# RPL_POWER_SOLENOIDS_REV2.net
KiCad netlist of a schematic drawn in Altium Designer
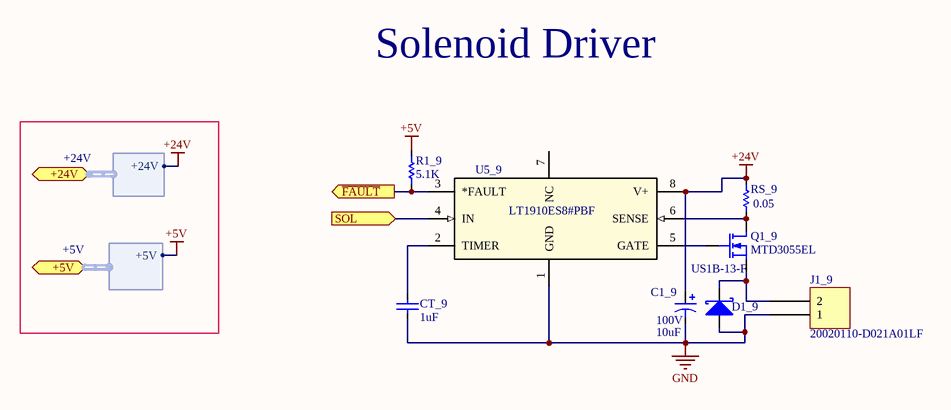
[diagram p0: RPL_POWER_SOLENOIDS_REV2.SchDoc]

(export (version "E")
  (design (tool "Eeschema 10.0.6"))
  (components
    (comp (ref "C1_9")
      (value "100V")
      (footprint "CAPs:(1210) CAPC3225X280")
      (fields (field (name "ALTIUM_VALUE") "10uF"))
      (libsource (lib "Generic_Library") (part "Cap Elec"))
    )
    (comp (ref "CT_9")
      (value "1uF")
      (footprint "(1210) CAPC3225X280")
      (fields (field (name "Comment") "Cap"))
      (libsource (lib "Generic_Library") (part "Cap"))
    )
    (comp (ref "D1_9")
      (value "US1B-13-F")
      (footprint "Diods:US1B-13-F")
      (libsource (lib "Generic_Library") (part "Diod"))
    )
    (comp (ref "J1_9")
      (value "20020110-D021A01LF")
      (footprint "FCI 06-381-2PIN")
      (description "TERM BLOCK HDR 2POS R/A 3.81MM")
      (fields (field (name "MANUFACTURER") "FCI") (field (name "VOLTAGE") "300V"))
      (libsource (lib "Celestial Library Database") (part "2 Pin"))
    )
    (comp (ref "Q1_9")
      (value "MTD3055EL")
      (footprint "TO229P990X239-3N")
      (libsource (lib "Generic_Library") (part "Mosfet"))
    )
    (comp (ref "R1_9")
      (value "5.1K")
      (footprint "SMD Resistors:RES 0805")
      (fields (field (name "Comment") "Res"))
      (libsource (lib "Generic_Library") (part "Res"))
    )
    (comp (ref "RS_9")
      (value "0.05")
      (footprint "SMD Resistors:RES 1206")
      (fields (field (name "Comment") "Res"))
      (libsource (lib "Generic_Library") (part "Res"))
    )
    (comp (ref "U5_9")
      (value "LT1910ES8#PBF")
      (footprint "LT1910:SO-8_S")
      (description "Imported")
      (fields (field (name "MANUFACTURER_PART_NUMBER") "lt1910es8#pbf"))
      (libsource (lib "Generic_Library") (part "LT1910ES8#PBF"))
    )
  )
  (nets
    (net (code "1") (name "+5V") (class "Default")
      (node (ref "R1_9") (pin "2") (pinfunction "2_2") (pintype "passive"))
    )
    (net (code "2") (name "+24V") (class "Default")
      (node (ref "C1_9") (pin "1") (pinfunction "1_1") (pintype "passive"))
      (node (ref "RS_9") (pin "2") (pinfunction "2_2") (pintype "passive"))
      (node (ref "U5_9") (pin "8") (pinfunction "V+_8") (pintype "power_in"))
    )
    (net (code "3") (name "/SOL") (class "Default")
      (node (ref "U5_9") (pin "4") (pinfunction "IN_4") (pintype "input"))
    )
    (net (code "6") (name "/~{FAULT}") (class "Default")
      (node (ref "R1_9") (pin "1") (pinfunction "1_1") (pintype "passive"))
      (node (ref "U5_9") (pin "3") (pinfunction "*FAULT_3") (pintype "passive"))
    )
    (net (code "7") (name "GND") (class "Default")
      (node (ref "C1_9") (pin "2") (pinfunction "2_2") (pintype "passive"))
      (node (ref "CT_9") (pin "1") (pinfunction "1_1") (pintype "passive"))
      (node (ref "D1_9") (pin "1") (pinfunction "A_1") (pintype "passive"))
      (node (ref "J1_9") (pin "1") (pinfunction "1_1") (pintype "passive"))
      (node (ref "U5_9") (pin "1") (pinfunction "GND_1") (pintype "power_in"))
    )
    (net (code "8") (name "Net-(D1_9-K)") (class "Default")
      (node (ref "D1_9") (pin "2") (pinfunction "K_2") (pintype "passive"))
      (node (ref "J1_9") (pin "2") (pinfunction "2_2") (pintype "passive"))
      (node (ref "Q1_9") (pin "3") (pinfunction "S_3") (pintype "passive"))
    )
    (net (code "9") (name "Net-(Q1_9-D)") (class "Default")
      (node (ref "Q1_9") (pin "1") (pinfunction "D_1") (pintype "passive"))
      (node (ref "RS_9") (pin "1") (pinfunction "1_1") (pintype "passive"))
      (node (ref "U5_9") (pin "6") (pinfunction "SENSE_6") (pintype "input"))
    )
    (net (code "10") (name "Net-(Q1_9-G)") (class "Default")
      (node (ref "Q1_9") (pin "2") (pinfunction "G_2") (pintype "passive"))
      (node (ref "U5_9") (pin "5") (pinfunction "GATE_5") (pintype "passive"))
    )
    (net (code "11") (name "Net-(U5_9-TIMER)") (class "Default")
      (node (ref "CT_9") (pin "2") (pinfunction "2_2") (pintype "passive"))
      (node (ref "U5_9") (pin "2") (pinfunction "TIMER_2") (pintype "passive"))
    )
    (net (code "12") (name "unconnected-(U5_9-NC-Pad7)") (class "Default")
      (node (ref "U5_9") (pin "7") (pinfunction "NC_7") (pintype "passive"))
    )
  )
)
